# Fans.net
KiCad netlist of a schematic drawn in Altium Designer
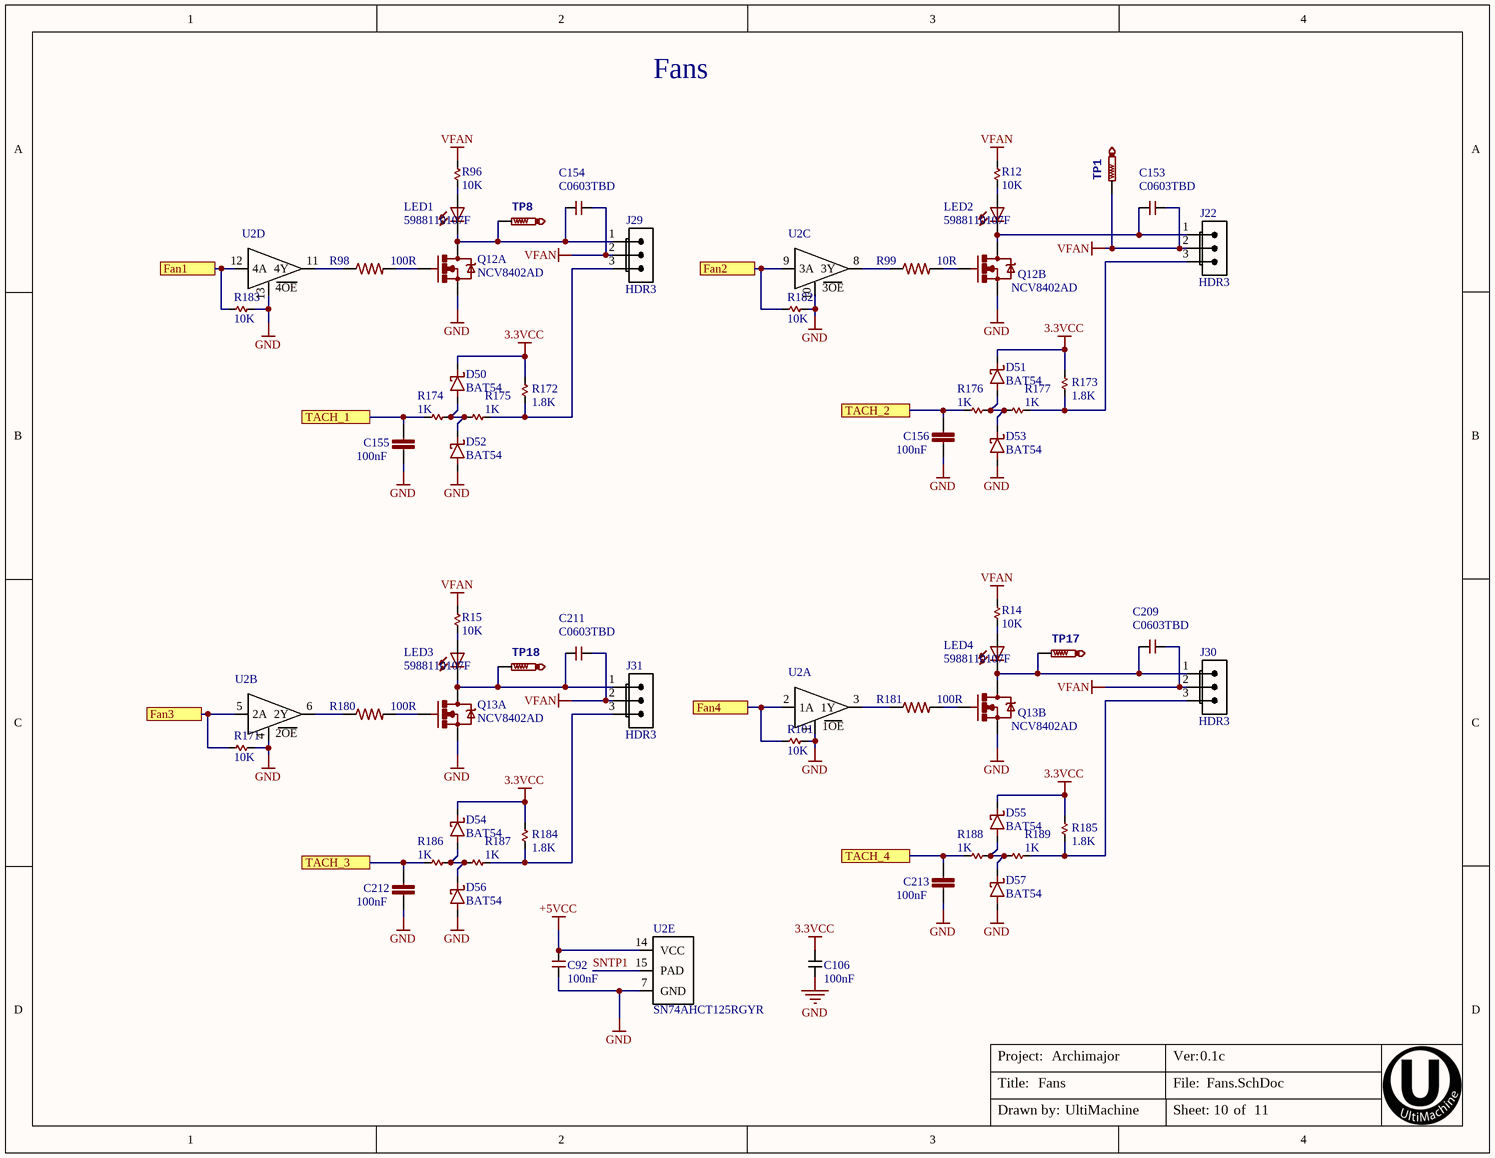
[diagram p0: Fans.SchDoc]

(export (version "E")
  (design (tool "Eeschema 10.0.6"))
  (components
    (comp (ref "C92")
      (value "100nF")
      (footprint "C0402")
      (description "CAP CER 0402 100nF 16V 10% X7R")
      (fields (field (name "MANUFACTURER") "Murata") (field (name "PART") "GRM155R71C104KA88D"))
      (libsource (lib "Capacitors") (part "100nF 0402 16V X7R"))
    )
    (comp (ref "C106")
      (value "100nF")
      (footprint "C0201 Large Pads")
      (description "CAP CER 0.1UF 6.3V 10% X5R 0201")
      (fields (field (name "PART") "CL03A104KQ3NNNC") (field (name "MANUFACTURER") "Samsung"))
      (libsource (lib "Capacitors") (part "100nF 6.3V X5R 0201"))
    )
    (comp (ref "C153")
      (value "C0603TBD")
      (footprint "C0603")
      (description "Capacitor Non Polarized")
      (fields (field (name "PART") "DNI-C0603TBD"))
      (libsource (lib "Capacitors") (part "C0603TBD"))
    )
    (comp (ref "C154")
      (value "C0603TBD")
      (footprint "C0603")
      (description "Capacitor Non Polarized")
      (fields (field (name "PART") "DNI-C0603TBD") (field (name "TOLERANCE") "5%"))
      (libsource (lib "Capacitors") (part "C0603TBD"))
    )
    (comp (ref "C155")
      (value "100nF")
      (footprint "C0402")
      (description "CAP CER 0402 100nF 16V 10% X7R")
      (fields (field (name "MANUFACTURER") "Murata") (field (name "PART") "GRM155R71C104KA88D"))
      (libsource (lib "3Delight") (part "GRM155R71C104KA88D"))
    )
    (comp (ref "C156")
      (value "100nF")
      (footprint "C0402")
      (description "CAP CER 0402 100nF 16V 10% X7R")
      (fields (field (name "MANUFACTURER") "Murata") (field (name "PART") "GRM155R71C104KA88D"))
      (libsource (lib "3Delight") (part "GRM155R71C104KA88D"))
    )
    (comp (ref "C209")
      (value "C0603TBD")
      (footprint "C0603")
      (description "Capacitor Non Polarized")
      (fields (field (name "PART") "DNI-C0603TBD"))
      (libsource (lib "Capacitors") (part "C0603TBD"))
    )
    (comp (ref "C211")
      (value "C0603TBD")
      (footprint "C0603")
      (description "Capacitor Non Polarized")
      (fields (field (name "PART") "DNI-C0603TBD"))
      (libsource (lib "Capacitors") (part "C0603TBD"))
    )
    (comp (ref "C212")
      (value "100nF")
      (footprint "C0402")
      (description "CAP CER 0402 100nF 16V 10% X7R")
      (fields (field (name "MANUFACTURER") "Murata") (field (name "PART") "GRM155R71C104KA88D"))
      (libsource (lib "3Delight") (part "GRM155R71C104KA88D"))
    )
    (comp (ref "C213")
      (value "100nF")
      (footprint "C0402")
      (description "CAP CER 0402 100nF 16V 10% X7R")
      (fields (field (name "MANUFACTURER") "Murata") (field (name "PART") "GRM155R71C104KA88D"))
      (libsource (lib "3Delight") (part "GRM155R71C104KA88D"))
    )
    (comp (ref "D50")
      (value "BAT54")
      (footprint "SOD523_IPC")
      (description "DIODE SCHOTTKY 30V 200MA SOD523")
      (fields (field (name "MANUFACTURER") "Diodes Incorporated") (field (name "PART") "BAT54WX-TP"))
      (libsource (lib "Diodes") (part "BAT54WX"))
    )
    (comp (ref "D51")
      (value "BAT54")
      (footprint "SOD523_IPC")
      (description "DIODE SCHOTTKY 30V 200MA SOD523")
      (fields (field (name "MANUFACTURER") "Diodes Incorporated") (field (name "PART") "BAT54WX-TP"))
      (libsource (lib "Diodes") (part "BAT54WX"))
    )
    (comp (ref "D52")
      (value "BAT54")
      (footprint "SOD523_IPC")
      (description "DIODE SCHOTTKY 30V 200MA SOD523")
      (fields (field (name "MANUFACTURER") "Diodes Incorporated") (field (name "PART") "BAT54WX-TP"))
      (libsource (lib "Diodes") (part "BAT54WX"))
    )
    (comp (ref "D53")
      (value "BAT54")
      (footprint "SOD523_IPC")
      (description "DIODE SCHOTTKY 30V 200MA SOD523")
      (fields (field (name "MANUFACTURER") "Diodes Incorporated") (field (name "PART") "BAT54WX-TP"))
      (libsource (lib "Diodes") (part "BAT54WX"))
    )
    (comp (ref "D54")
      (value "BAT54")
      (footprint "SOD523_IPC")
      (description "DIODE SCHOTTKY 30V 200MA SOD523")
      (fields (field (name "MANUFACTURER") "Diodes Incorporated") (field (name "PART") "BAT54WX-TP"))
      (libsource (lib "Diodes") (part "BAT54WX"))
    )
    (comp (ref "D55")
      (value "BAT54")
      (footprint "SOD523_IPC")
      (description "DIODE SCHOTTKY 30V 200MA SOD523")
      (fields (field (name "MANUFACTURER") "Diodes Incorporated") (field (name "PART") "BAT54WX-TP"))
      (libsource (lib "Diodes") (part "BAT54WX"))
    )
    (comp (ref "D56")
      (value "BAT54")
      (footprint "SOD523_IPC")
      (description "DIODE SCHOTTKY 30V 200MA SOD523")
      (fields (field (name "MANUFACTURER") "Diodes Incorporated") (field (name "PART") "BAT54WX-TP"))
      (libsource (lib "Diodes") (part "BAT54WX"))
    )
    (comp (ref "D57")
      (value "BAT54")
      (footprint "SOD523_IPC")
      (description "DIODE SCHOTTKY 30V 200MA SOD523")
      (fields (field (name "MANUFACTURER") "Diodes Incorporated") (field (name "PART") "BAT54WX-TP"))
      (libsource (lib "Diodes") (part "BAT54WX"))
    )
    (comp (ref "J22")
      (value "HDR3")
      (footprint "70543-02 PIN-IN-PASTE")
      (description "3 Positions Header, Shrouded Connector 0.100\" (2.54mm) Through Hole Gold - Pin in Paste")
      (fields (field (name "MANUFACTURER") "Molex") (field (name "PART") "0705430002"))
      (libsource (lib "Connectors") (part "CONN 3POS VERT 0.1{dblquote} SHRD LOCKING PIP"))
    )
    (comp (ref "J29")
      (value "HDR3")
      (footprint "70543-02 PIN-IN-PASTE")
      (description "3 Positions Header, Shrouded Connector 0.100\" (2.54mm) Through Hole Gold - Pin in Paste")
      (fields (field (name "MANUFACTURER") "Molex") (field (name "PART") "0705430002"))
      (libsource (lib "Connectors") (part "CONN 3POS VERT 0.1{dblquote} SHRD LOCKING PIP"))
    )
    (comp (ref "J30")
      (value "HDR3")
      (footprint "70543-02 PIN-IN-PASTE")
      (description "3 Positions Header, Shrouded Connector 0.100\" (2.54mm) Through Hole Gold - Pin in Paste")
      (fields (field (name "MANUFACTURER") "Molex") (field (name "PART") "0705430002"))
      (libsource (lib "Connectors") (part "CONN 3POS VERT 0.1{dblquote} SHRD LOCKING PIP"))
    )
    (comp (ref "J31")
      (value "HDR3")
      (footprint "70543-02 PIN-IN-PASTE")
      (description "3 Positions Header, Shrouded Connector 0.100\" (2.54mm) Through Hole Gold - Pin in Paste")
      (fields (field (name "MANUFACTURER") "Molex") (field (name "PART") "0705430002"))
      (libsource (lib "Connectors") (part "CONN 3POS VERT 0.1{dblquote} SHRD LOCKING PIP"))
    )
    (comp (ref "LED1")
      (value "RED")
      (footprint "LED2012120")
      (description "LED 0805 Red")
      (fields
        (field (name "MANUFACTURER") "Dialight")
        (field (name "PART") "5988110107F")
        (field (name "TOLERANCE") "NA")
      )
      (libsource (lib "3Delight") (part "5988110107F"))
    )
    (comp (ref "LED2")
      (value "RED")
      (footprint "LED2012120")
      (description "LED 0805 Red")
      (fields
        (field (name "MANUFACTURER") "Dialight")
        (field (name "PART") "5988110107F")
        (field (name "TOLERANCE") "NA")
      )
      (libsource (lib "3Delight") (part "5988110107F"))
    )
    (comp (ref "LED3")
      (value "RED")
      (footprint "LED2012120")
      (description "LED 0805 Red")
      (fields
        (field (name "MANUFACTURER") "Dialight")
        (field (name "PART") "5988110107F")
        (field (name "TOLERANCE") "NA")
      )
      (libsource (lib "3Delight") (part "5988110107F"))
    )
    (comp (ref "LED4")
      (value "RED")
      (footprint "LED2012120")
      (description "LED 0805 Red")
      (fields
        (field (name "MANUFACTURER") "Dialight")
        (field (name "PART") "5988110107F")
        (field (name "TOLERANCE") "NA")
      )
      (libsource (lib "3Delight") (part "5988110107F"))
    )
    (comp (ref "Q12")
      (value "NCV8402AD")
      (footprint "NCV8402AD-SOIC8")
      (description "IC DVR LOW SIDE 8-SOIC")
      (fields (field (name "MANUFACTURER") "On Semi") (field (name "PART") "NCV8402ADDR2G"))
      (libsource (lib "Transistors") (part "NCV8402AD"))
    )
    (comp (ref "Q13")
      (value "NCV8402AD")
      (footprint "NCV8402AD-SOIC8")
      (description "IC DVR LOW SIDE 8-SOIC")
      (fields (field (name "MANUFACTURER") "On Semi") (field (name "PART") "NCV8402ADDR2G"))
      (libsource (lib "Transistors") (part "NCV8402AD"))
    )
    (comp (ref "R12")
      (value "10K")
      (footprint "R0402")
      (description "RES SMD 10K OHM 1% 1/16W 0402")
      (fields (field (name "MANUFACTURER") "Yageo") (field (name "PART") "RC0402FR-0710KP"))
      (libsource (lib "Resistors") (part "10k 1% 0402"))
    )
    (comp (ref "R14")
      (value "10K")
      (footprint "R0402")
      (description "RES SMD 10K OHM 1% 1/16W 0402")
      (fields (field (name "MANUFACTURER") "Yageo") (field (name "PART") "RC0402FR-0710KP"))
      (libsource (lib "Resistors") (part "10k 1% 0402"))
    )
    (comp (ref "R15")
      (value "10K")
      (footprint "R0402")
      (description "RES SMD 10K OHM 1% 1/16W 0402")
      (fields (field (name "MANUFACTURER") "Yageo") (field (name "PART") "RC0402FR-0710KP"))
      (libsource (lib "Resistors") (part "10k 1% 0402"))
    )
    (comp (ref "R96")
      (value "10K")
      (footprint "R0402")
      (description "RES SMD 10K OHM 1% 1/16W 0402")
      (fields (field (name "MANUFACTURER") "Yageo") (field (name "PART") "RC0402FR-0710KP"))
      (libsource (lib "Resistors") (part "10k 1% 0402"))
    )
    (comp (ref "R98")
      (value "100R")
      (footprint "R0402")
      (description "RES SMD 100 OHM 1% 1/16W 0402")
      (fields (field (name "MANUFACTURER") "Yageo") (field (name "PART") "RC0402FR-07100RL"))
      (libsource (lib "Archim") (part "RES 100R 0402 1%"))
    )
    (comp (ref "R99")
      (value "10R")
      (footprint "R0402")
      (description "RES SMD 100 OHM 1% 1/16W 0402")
      (fields (field (name "MANUFACTURER") "Yageo") (field (name "PART") "RC0402FR-0710RL"))
      (libsource (lib "Archim") (part "RES 100R 0402 1%"))
    )
    (comp (ref "R101")
      (value "10K")
      (footprint "R0402")
      (description "RES SMD 10K OHM 1% 1/16W 0402")
      (fields (field (name "MANUFACTURER") "Yageo") (field (name "PART") "RC0402FR-0710KP"))
      (libsource (lib "Resistors") (part "10k 1% 0402"))
    )
    (comp (ref "R171")
      (value "10K")
      (footprint "R0402")
      (description "RES SMD 10K OHM 1% 1/16W 0402")
      (fields (field (name "MANUFACTURER") "Yageo") (field (name "PART") "RC0402FR-0710KP"))
      (libsource (lib "Resistors") (part "10k 1% 0402"))
    )
    (comp (ref "R172")
      (value "1.8K")
      (footprint "R0402")
      (description "RES SMD 1.8K OHM 1% 1/16W 0402")
      (fields (field (name "MANUFACTURER") "Yageo") (field (name "PART") "RC0402FR-071K8L"))
      (libsource (lib "3Delight") (part "RC0402FR-071K8L"))
    )
    (comp (ref "R173")
      (value "1.8K")
      (footprint "R0402")
      (description "RES SMD 1.8K OHM 1% 1/16W 0402")
      (fields (field (name "MANUFACTURER") "Yageo") (field (name "PART") "RC0402FR-071K8L"))
      (libsource (lib "3Delight") (part "RC0402FR-071K8L"))
    )
    (comp (ref "R174")
      (value "1K")
      (footprint "R0402")
      (description "RES SMD 1K OHM 1% 1/16W 0402")
      (fields (field (name "MANUFACTURER") "Yageo") (field (name "PART") "RC0402FR-071KL"))
      (libsource (lib "3Delight") (part "RC0402FR-071KL"))
    )
    (comp (ref "R175")
      (value "1K")
      (footprint "R0402")
      (description "RES SMD 1K OHM 1% 1/16W 0402")
      (fields (field (name "MANUFACTURER") "Yageo") (field (name "PART") "RC0402FR-071KL"))
      (libsource (lib "3Delight") (part "RC0402FR-071KL"))
    )
    (comp (ref "R176")
      (value "1K")
      (footprint "R0402")
      (description "RES SMD 1K OHM 1% 1/16W 0402")
      (fields (field (name "MANUFACTURER") "Yageo") (field (name "PART") "RC0402FR-071KL"))
      (libsource (lib "3Delight") (part "RC0402FR-071KL"))
    )
    (comp (ref "R177")
      (value "1K")
      (footprint "R0402")
      (description "RES SMD 1K OHM 1% 1/16W 0402")
      (fields (field (name "MANUFACTURER") "Yageo") (field (name "PART") "RC0402FR-071KL"))
      (libsource (lib "3Delight") (part "RC0402FR-071KL"))
    )
    (comp (ref "R180")
      (value "100R")
      (footprint "R0402")
      (description "RES SMD 100 OHM 1% 1/16W 0402")
      (fields (field (name "MANUFACTURER") "Yageo") (field (name "PART") "RC0402FR-07100RL"))
      (libsource (lib "Archim") (part "RES 100R 0402 1%"))
    )
    (comp (ref "R181")
      (value "100R")
      (footprint "R0402")
      (description "RES SMD 100 OHM 1% 1/16W 0402")
      (fields (field (name "MANUFACTURER") "Yageo") (field (name "PART") "RC0402FR-07100RL"))
      (libsource (lib "Archim") (part "RES 100R 0402 1%"))
    )
    (comp (ref "R182")
      (value "10K")
      (footprint "R0402")
      (description "RES SMD 10K OHM 1% 1/16W 0402")
      (fields (field (name "MANUFACTURER") "Yageo") (field (name "PART") "RC0402FR-0710KP"))
      (libsource (lib "Resistors") (part "10k 1% 0402"))
    )
    (comp (ref "R183")
      (value "10K")
      (footprint "R0402")
      (description "RES SMD 10K OHM 1% 1/16W 0402")
      (fields (field (name "MANUFACTURER") "Yageo") (field (name "PART") "RC0402FR-0710KP"))
      (libsource (lib "Resistors") (part "10k 1% 0402"))
    )
    (comp (ref "R184")
      (value "1.8K")
      (footprint "R0402")
      (description "RES SMD 1.8K OHM 1% 1/16W 0402")
      (fields (field (name "MANUFACTURER") "Yageo") (field (name "PART") "RC0402FR-071K8L"))
      (libsource (lib "3Delight") (part "RC0402FR-071K8L"))
    )
    (comp (ref "R185")
      (value "1.8K")
      (footprint "R0402")
      (description "RES SMD 1.8K OHM 1% 1/16W 0402")
      (fields (field (name "MANUFACTURER") "Yageo") (field (name "PART") "RC0402FR-071K8L"))
      (libsource (lib "3Delight") (part "RC0402FR-071K8L"))
    )
    (comp (ref "R186")
      (value "1K")
      (footprint "R0402")
      (description "RES SMD 1K OHM 1% 1/16W 0402")
      (fields (field (name "MANUFACTURER") "Yageo") (field (name "PART") "RC0402FR-071KL"))
      (libsource (lib "3Delight") (part "RC0402FR-071KL"))
    )
    (comp (ref "R187")
      (value "1K")
      (footprint "R0402")
      (description "RES SMD 1K OHM 1% 1/16W 0402")
      (fields (field (name "MANUFACTURER") "Yageo") (field (name "PART") "RC0402FR-071KL"))
      (libsource (lib "3Delight") (part "RC0402FR-071KL"))
    )
    (comp (ref "R188")
      (value "1K")
      (footprint "R0402")
      (description "RES SMD 1K OHM 1% 1/16W 0402")
      (fields (field (name "MANUFACTURER") "Yageo") (field (name "PART") "RC0402FR-071KL"))
      (libsource (lib "3Delight") (part "RC0402FR-071KL"))
    )
    (comp (ref "R189")
      (value "1K")
      (footprint "R0402")
      (description "RES SMD 1K OHM 1% 1/16W 0402")
      (fields (field (name "MANUFACTURER") "Yageo") (field (name "PART") "RC0402FR-071KL"))
      (libsource (lib "3Delight") (part "RC0402FR-071KL"))
    )
    (comp (ref "TP1")
      (value "TestPoint")
      (footprint "TP1-27")
      (description "Test Point")
      (libsource (lib "3Delight") (part "TestPoint"))
    )
    (comp (ref "TP8")
      (value "TestPoint")
      (footprint "TP1-27")
      (description "Test Point")
      (libsource (lib "") (part "TestPoint_1"))
    )
    (comp (ref "TP17")
      (value "TestPoint")
      (footprint "TP1-27")
      (description "Test Point")
      (libsource (lib "") (part "TestPoint_1"))
    )
    (comp (ref "TP18")
      (value "TestPoint")
      (footprint "TP1-27")
      (description "Test Point")
      (libsource (lib "") (part "TestPoint_1"))
    )
    (comp (ref "U2")
      (value "SN74AHCT125RGYR")
      (footprint "QFN50P350X350X100_RGY_S-PVQFN-N14")
      (description "Quadruple Bus Buffer Gates With 3-State Outputs 14-VQFN -40 to 125")
      (fields (field (name "MANUFACTURER") "Texas Instruments") (field (name "TOLERANCE") "-NA-"))
      (libsource (lib "ICs-Logic") (part "SN74AHCT125"))
    )
  )
  (nets
    (net (code "1") (name "+5VCC") (class "Default")
      (node (ref "C92") (pin "2") (pinfunction "2_2") (pintype "passive"))
      (node (ref "U2") (pin "14") (pinfunction "VCC_14") (pintype "passive"))
    )
    (net (code "2") (name "/Fan1") (class "Default")
      (node (ref "R183") (pin "1") (pinfunction "1_1") (pintype "passive"))
      (node (ref "U2") (pin "12") (pinfunction "4A_12") (pintype "passive"))
    )
    (net (code "3") (name "/Fan2") (class "Default")
      (node (ref "R182") (pin "1") (pinfunction "1_1") (pintype "passive"))
      (node (ref "U2") (pin "9") (pinfunction "3A_9") (pintype "passive"))
    )
    (net (code "4") (name "/Fan3") (class "Default")
      (node (ref "R171") (pin "1") (pinfunction "1_1") (pintype "passive"))
      (node (ref "U2") (pin "5") (pinfunction "2A_5") (pintype "passive"))
    )
    (net (code "5") (name "/Fan4") (class "Default")
      (node (ref "R101") (pin "1") (pinfunction "1_1") (pintype "passive"))
      (node (ref "U2") (pin "2") (pinfunction "1A_2") (pintype "passive"))
    )
    (net (code "6") (name "/SNTP1") (class "Default")
      (node (ref "U2") (pin "15") (pinfunction "PAD_15") (pintype "passive"))
    )
    (net (code "7") (name "/TACH_1") (class "Default")
      (node (ref "C155") (pin "1") (pinfunction "1_1") (pintype "passive"))
      (node (ref "R174") (pin "1") (pinfunction "1_1") (pintype "passive"))
    )
    (net (code "8") (name "/TACH_2") (class "Default")
      (node (ref "C156") (pin "1") (pinfunction "1_1") (pintype "passive"))
      (node (ref "R176") (pin "1") (pinfunction "1_1") (pintype "passive"))
    )
    (net (code "9") (name "/TACH_3") (class "Default")
      (node (ref "C212") (pin "1") (pinfunction "1_1") (pintype "passive"))
      (node (ref "R186") (pin "1") (pinfunction "1_1") (pintype "passive"))
    )
    (net (code "10") (name "/TACH_4") (class "Default")
      (node (ref "C213") (pin "1") (pinfunction "1_1") (pintype "passive"))
      (node (ref "R188") (pin "1") (pinfunction "1_1") (pintype "passive"))
    )
    (net (code "11") (name "3.3VCC") (class "Default")
      (node (ref "C106") (pin "2") (pinfunction "2_2") (pintype "passive"))
      (node (ref "D50") (pin "K") (pinfunction "K_K") (pintype "passive"))
      (node (ref "D51") (pin "K") (pinfunction "K_K") (pintype "passive"))
      (node (ref "D54") (pin "K") (pinfunction "K_K") (pintype "passive"))
      (node (ref "D55") (pin "K") (pinfunction "K_K") (pintype "passive"))
      (node (ref "R172") (pin "2") (pinfunction "2_2") (pintype "passive"))
      (node (ref "R173") (pin "2") (pinfunction "2_2") (pintype "passive"))
      (node (ref "R184") (pin "2") (pinfunction "2_2") (pintype "passive"))
      (node (ref "R185") (pin "2") (pinfunction "2_2") (pintype "passive"))
    )
    (net (code "12") (name "GND") (class "Default")
      (node (ref "C106") (pin "1") (pinfunction "1_1") (pintype "passive"))
      (node (ref "C155") (pin "2") (pinfunction "2_2") (pintype "passive"))
      (node (ref "C156") (pin "2") (pinfunction "2_2") (pintype "passive"))
      (node (ref "C212") (pin "2") (pinfunction "2_2") (pintype "passive"))
      (node (ref "C213") (pin "2") (pinfunction "2_2") (pintype "passive"))
      (node (ref "C92") (pin "1") (pinfunction "1_1") (pintype "passive"))
      (node (ref "D52") (pin "A") (pinfunction "A_A") (pintype "passive"))
      (node (ref "D56") (pin "A") (pinfunction "A_A") (pintype "passive"))
      (node (ref "D57") (pin "A") (pinfunction "A_A") (pintype "passive"))
      (node (ref "Q12") (pin "1") (pinfunction "S_1") (pintype "passive"))
      (node (ref "Q12") (pin "3") (pinfunction "S_3") (pintype "passive"))
      (node (ref "Q13") (pin "1") (pinfunction "S_1") (pintype "passive"))
      (node (ref "Q13") (pin "3") (pinfunction "S_3") (pintype "passive"))
      (node (ref "R101") (pin "2") (pinfunction "2_2") (pintype "passive"))
      (node (ref "R171") (pin "2") (pinfunction "2_2") (pintype "passive"))
      (node (ref "R182") (pin "2") (pinfunction "2_2") (pintype "passive"))
      (node (ref "R183") (pin "2") (pinfunction "2_2") (pintype "passive"))
      (node (ref "U2") (pin "1") (pinfunction "1OE_1") (pintype "passive"))
      (node (ref "U2") (pin "10") (pinfunction "3OE_10") (pintype "passive"))
      (node (ref "U2") (pin "13") (pinfunction "4OE_13") (pintype "passive"))
      (node (ref "U2") (pin "4") (pinfunction "2OE_4") (pintype "passive"))
      (node (ref "U2") (pin "7") (pinfunction "GND_7") (pintype "passive"))
    )
    (net (code "13") (name "Net-(D50-PadA)") (class "Default")
      (node (ref "D50") (pin "A") (pinfunction "A_A") (pintype "passive"))
      (node (ref "D52") (pin "K") (pinfunction "K_K") (pintype "passive"))
      (node (ref "R174") (pin "2") (pinfunction "2_2") (pintype "passive"))
      (node (ref "R175") (pin "1") (pinfunction "1_1") (pintype "passive"))
    )
    (net (code "14") (name "Net-(D51-PadA)") (class "Default")
      (node (ref "D51") (pin "A") (pinfunction "A_A") (pintype "passive"))
      (node (ref "D53") (pin "K") (pinfunction "K_K") (pintype "passive"))
      (node (ref "R176") (pin "2") (pinfunction "2_2") (pintype "passive"))
      (node (ref "R177") (pin "1") (pinfunction "1_1") (pintype "passive"))
    )
    (net (code "15") (name "Net-(D54-PadA)") (class "Default")
      (node (ref "D54") (pin "A") (pinfunction "A_A") (pintype "passive"))
      (node (ref "D56") (pin "K") (pinfunction "K_K") (pintype "passive"))
      (node (ref "R186") (pin "2") (pinfunction "2_2") (pintype "passive"))
      (node (ref "R187") (pin "1") (pinfunction "1_1") (pintype "passive"))
    )
    (net (code "16") (name "Net-(D55-PadA)") (class "Default")
      (node (ref "D55") (pin "A") (pinfunction "A_A") (pintype "passive"))
      (node (ref "D57") (pin "K") (pinfunction "K_K") (pintype "passive"))
      (node (ref "R188") (pin "2") (pinfunction "2_2") (pintype "passive"))
      (node (ref "R189") (pin "1") (pinfunction "1_1") (pintype "passive"))
    )
    (net (code "17") (name "Net-(J22-S-Pad3)") (class "Default")
      (node (ref "J22") (pin "3") (pinfunction "S_3") (pintype "passive"))
      (node (ref "R173") (pin "1") (pinfunction "1_1") (pintype "passive"))
      (node (ref "R177") (pin "2") (pinfunction "2_2") (pintype "passive"))
    )
    (net (code "18") (name "Net-(J29-S-Pad3)") (class "Default")
      (node (ref "J29") (pin "3") (pinfunction "S_3") (pintype "passive"))
      (node (ref "R172") (pin "1") (pinfunction "1_1") (pintype "passive"))
      (node (ref "R175") (pin "2") (pinfunction "2_2") (pintype "passive"))
    )
    (net (code "19") (name "Net-(J30-S-Pad3)") (class "Default")
      (node (ref "J30") (pin "3") (pinfunction "S_3") (pintype "passive"))
      (node (ref "R185") (pin "1") (pinfunction "1_1") (pintype "passive"))
      (node (ref "R189") (pin "2") (pinfunction "2_2") (pintype "passive"))
    )
    (net (code "20") (name "Net-(J31-S-Pad3)") (class "Default")
      (node (ref "J31") (pin "3") (pinfunction "S_3") (pintype "passive"))
      (node (ref "R184") (pin "1") (pinfunction "1_1") (pintype "passive"))
      (node (ref "R187") (pin "2") (pinfunction "2_2") (pintype "passive"))
    )
    (net (code "21") (name "Net-(LED1-PadA)") (class "Default")
      (node (ref "LED1") (pin "A") (pinfunction "A_A") (pintype "passive"))
      (node (ref "R96") (pin "1") (pinfunction "1_1") (pintype "passive"))
    )
    (net (code "22") (name "Net-(LED2-PadA)") (class "Default")
      (node (ref "LED2") (pin "A") (pinfunction "A_A") (pintype "passive"))
      (node (ref "R12") (pin "1") (pinfunction "1_1") (pintype "passive"))
    )
    (net (code "23") (name "Net-(LED3-PadA)") (class "Default")
      (node (ref "LED3") (pin "A") (pinfunction "A_A") (pintype "passive"))
      (node (ref "R15") (pin "1") (pinfunction "1_1") (pintype "passive"))
    )
    (net (code "24") (name "Net-(LED4-PadA)") (class "Default")
      (node (ref "LED4") (pin "A") (pinfunction "A_A") (pintype "passive"))
      (node (ref "R14") (pin "1") (pinfunction "1_1") (pintype "passive"))
    )
    (net (code "25") (name "Net-(Q12A-D)") (class "Default")
      (node (ref "C154") (pin "2") (pinfunction "2_2") (pintype "passive"))
      (node (ref "J29") (pin "1") (pinfunction "S_1") (pintype "passive"))
      (node (ref "LED1") (pin "C") (pinfunction "C_C") (pintype "passive"))
      (node (ref "Q12") (pin "7") (pinfunction "D_7") (pintype "passive"))
      (node (ref "TP8") (pin "TP") (pinfunction "TP_TP") (pintype "passive"))
    )
    (net (code "26") (name "Net-(Q12A-G)") (class "Default")
      (node (ref "Q12") (pin "2") (pinfunction "G_2") (pintype "passive"))
      (node (ref "R98") (pin "2") (pinfunction "2_2") (pintype "passive"))
    )
    (net (code "27") (name "Net-(Q12B-D)") (class "Default")
      (node (ref "C153") (pin "2") (pinfunction "2_2") (pintype "passive"))
      (node (ref "J22") (pin "1") (pinfunction "S_1") (pintype "passive"))
      (node (ref "LED2") (pin "C") (pinfunction "C_C") (pintype "passive"))
      (node (ref "Q12") (pin "5") (pinfunction "D_5") (pintype "passive"))
    )
    (net (code "28") (name "Net-(Q12B-G)") (class "Default")
      (node (ref "Q12") (pin "4") (pinfunction "G_4") (pintype "passive"))
      (node (ref "R99") (pin "2") (pinfunction "2_2") (pintype "passive"))
    )
    (net (code "29") (name "Net-(Q13A-D)") (class "Default")
      (node (ref "C211") (pin "2") (pinfunction "2_2") (pintype "passive"))
      (node (ref "J31") (pin "1") (pinfunction "S_1") (pintype "passive"))
      (node (ref "LED3") (pin "C") (pinfunction "C_C") (pintype "passive"))
      (node (ref "Q13") (pin "7") (pinfunction "D_7") (pintype "passive"))
      (node (ref "TP18") (pin "TP") (pinfunction "TP_TP") (pintype "passive"))
    )
    (net (code "30") (name "Net-(Q13A-G)") (class "Default")
      (node (ref "Q13") (pin "2") (pinfunction "G_2") (pintype "passive"))
      (node (ref "R180") (pin "2") (pinfunction "2_2") (pintype "passive"))
    )
    (net (code "31") (name "Net-(Q13B-D)") (class "Default")
      (node (ref "C209") (pin "2") (pinfunction "2_2") (pintype "passive"))
      (node (ref "J30") (pin "1") (pinfunction "S_1") (pintype "passive"))
      (node (ref "LED4") (pin "C") (pinfunction "C_C") (pintype "passive"))
      (node (ref "Q13") (pin "5") (pinfunction "D_5") (pintype "passive"))
      (node (ref "TP17") (pin "TP") (pinfunction "TP_TP") (pintype "passive"))
    )
    (net (code "32") (name "Net-(Q13B-G)") (class "Default")
      (node (ref "Q13") (pin "4") (pinfunction "G_4") (pintype "passive"))
      (node (ref "R181") (pin "2") (pinfunction "2_2") (pintype "passive"))
    )
    (net (code "33") (name "Net-(U2A-1Y)") (class "Default")
      (node (ref "R181") (pin "1") (pinfunction "1_1") (pintype "passive"))
      (node (ref "U2") (pin "3") (pinfunction "1Y_3") (pintype "passive"))
    )
    (net (code "34") (name "Net-(U2B-2Y)") (class "Default")
      (node (ref "R180") (pin "1") (pinfunction "1_1") (pintype "passive"))
      (node (ref "U2") (pin "6") (pinfunction "2Y_6") (pintype "passive"))
    )
    (net (code "35") (name "Net-(U2C-3Y)") (class "Default")
      (node (ref "R99") (pin "1") (pinfunction "1_1") (pintype "passive"))
      (node (ref "U2") (pin "8") (pinfunction "3Y_8") (pintype "passive"))
    )
    (net (code "36") (name "Net-(U2D-4Y)") (class "Default")
      (node (ref "R98") (pin "1") (pinfunction "1_1") (pintype "passive"))
      (node (ref "U2") (pin "11") (pinfunction "4Y_11") (pintype "passive"))
    )
    (net (code "37") (name "VFAN") (class "Default")
      (node (ref "C153") (pin "1") (pinfunction "1_1") (pintype "passive"))
      (node (ref "C154") (pin "1") (pinfunction "1_1") (pintype "passive"))
      (node (ref "C209") (pin "1") (pinfunction "1_1") (pintype "passive"))
      (node (ref "C211") (pin "1") (pinfunction "1_1") (pintype "passive"))
      (node (ref "J22") (pin "2") (pinfunction "S_2") (pintype "passive"))
      (node (ref "J29") (pin "2") (pinfunction "S_2") (pintype "passive"))
      (node (ref "J30") (pin "2") (pinfunction "S_2") (pintype "passive"))
      (node (ref "J31") (pin "2") (pinfunction "S_2") (pintype "passive"))
      (node (ref "R12") (pin "2") (pinfunction "2_2") (pintype "passive"))
      (node (ref "R14") (pin "2") (pinfunction "2_2") (pintype "passive"))
      (node (ref "R15") (pin "2") (pinfunction "2_2") (pintype "passive"))
      (node (ref "R96") (pin "2") (pinfunction "2_2") (pintype "passive"))
      (node (ref "TP1") (pin "TP") (pinfunction "TP_TP") (pintype "passive"))
    )
    (net (code "38") (name "unconnected-(D53-PadA)") (class "Default")
      (node (ref "D53") (pin "A") (pinfunction "A_A") (pintype "passive"))
    )
  )
)
